# uC.net
KiCad netlist of a schematic drawn in Altium Designer
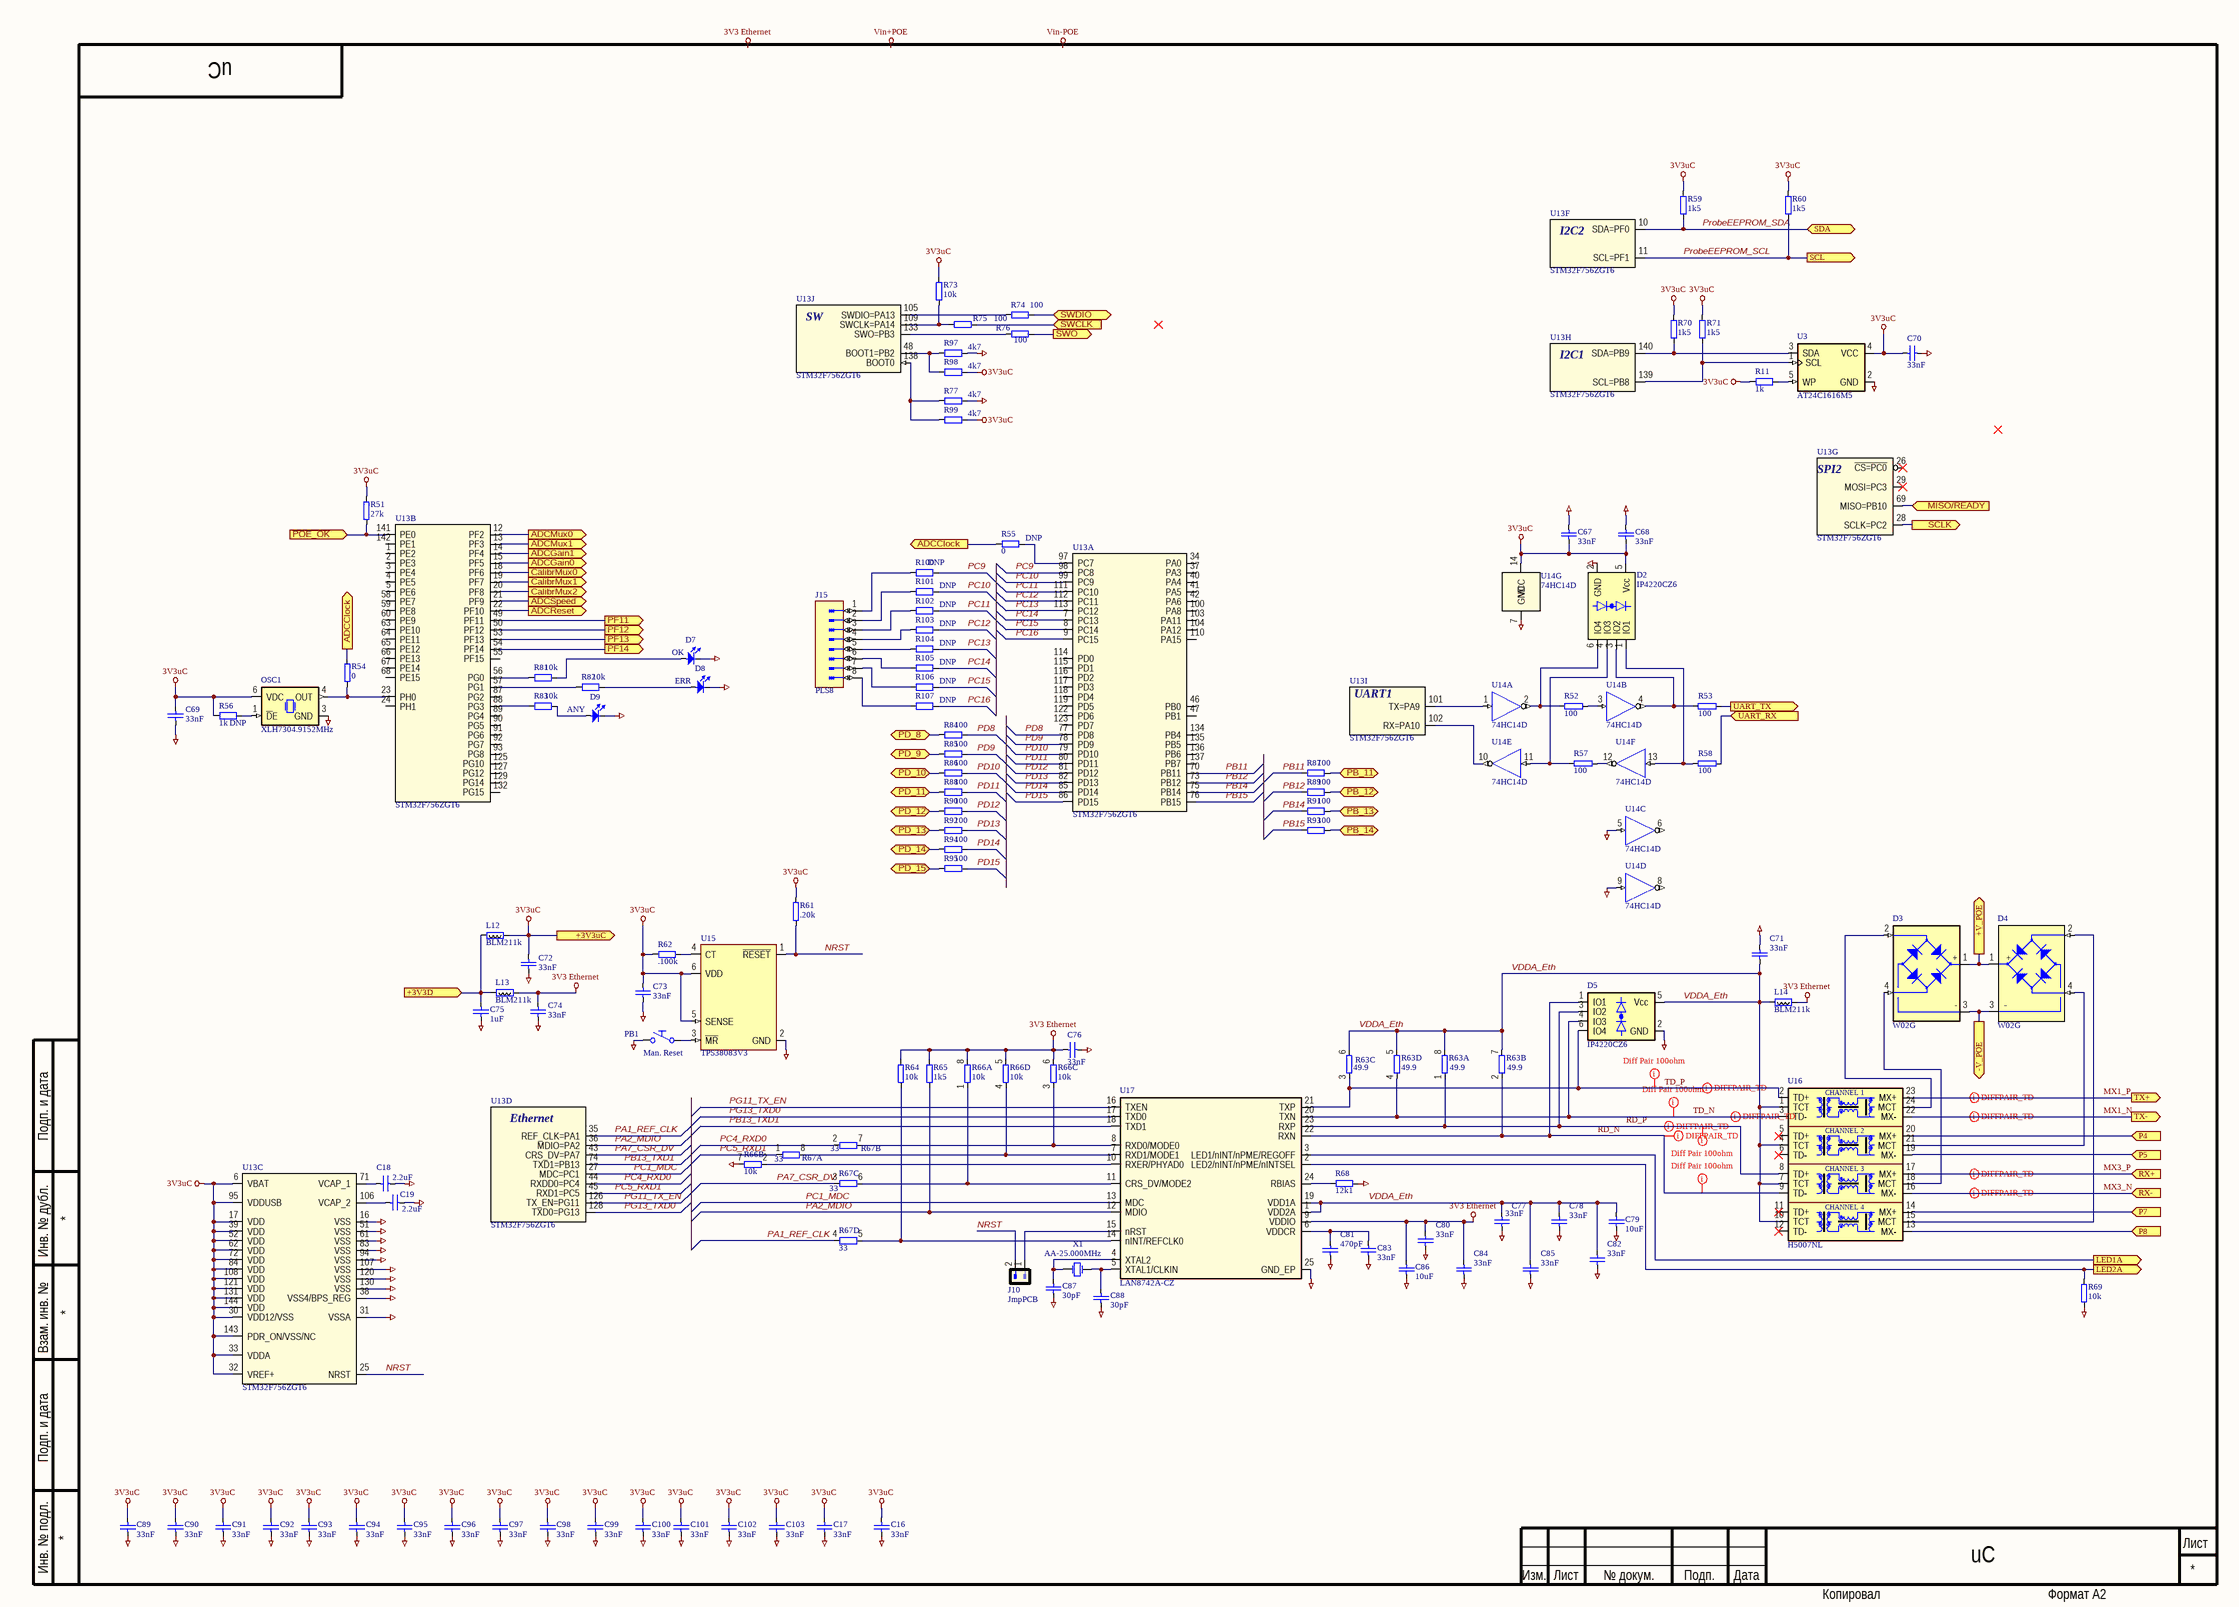
[diagram p0: uC.SchDoc]

(export (version "E")
  (design (tool "Eeschema 10.0.6"))
  (components
    (comp (ref "C16")
      (value "33nF")
      (footprint "CAPC1608X87N")
      (description "Чип конденсатор 0603")
      (fields (field (name "VOLTAGE") "50V") (field (name "TOLERANCE") "20%"))
      (libsource (lib "DDSintLib") (part "C0603"))
    )
    (comp (ref "C17")
      (value "33nF")
      (footprint "CAPC1608X87N")
      (description "Чип конденсатор 0603")
      (fields (field (name "VOLTAGE") "50V") (field (name "TOLERANCE") "20%"))
      (libsource (lib "DDSintLib") (part "C0603"))
    )
    (comp (ref "C18")
      (value "2.2uF")
      (footprint "SMD0805CAP")
      (description "Чип конденсатор 0805")
      (fields (field (name "VOLTAGE") "25V") (field (name "TOLERANCE") "20%"))
      (libsource (lib "DDSintLib") (part "C0805"))
    )
    (comp (ref "C19")
      (value "2.2uF")
      (footprint "SMD0805CAP")
      (description "Чип конденсатор 0805")
      (fields (field (name "VOLTAGE") "25V") (field (name "TOLERANCE") "20%"))
      (libsource (lib "DDSintLib") (part "C0805"))
    )
    (comp (ref "C67")
      (value "33nF")
      (footprint "CAPC1608X87N")
      (description "Чип конденсатор 0603")
      (fields (field (name "VOLTAGE") "50V") (field (name "TOLERANCE") "20%"))
      (libsource (lib "DDSintLib") (part "C0603"))
    )
    (comp (ref "C68")
      (value "33nF")
      (footprint "CAPC1608X87N")
      (description "Чип конденсатор 0603")
      (fields (field (name "VOLTAGE") "50V") (field (name "TOLERANCE") "20%"))
      (libsource (lib "DDSintLib") (part "C0603"))
    )
    (comp (ref "C69")
      (value "33nF")
      (footprint "CAPC1608X87N")
      (description "Чип конденсатор 0603")
      (fields (field (name "VOLTAGE") "50V") (field (name "TOLERANCE") "20%"))
      (libsource (lib "DDSintLib") (part "C0603"))
    )
    (comp (ref "C70")
      (value "33nF")
      (footprint "CAPC1608X87N")
      (description "Чип конденсатор 0603")
      (fields (field (name "VOLTAGE") "50V") (field (name "TOLERANCE") "20%"))
      (libsource (lib "DDSintLib") (part "C0603"))
    )
    (comp (ref "C71")
      (value "33nF")
      (footprint "CAPC1608X87N")
      (description "Чип конденсатор 0603")
      (fields (field (name "VOLTAGE") "50V") (field (name "TOLERANCE") "20%"))
      (libsource (lib "DDSintLib") (part "C0603"))
    )
    (comp (ref "C72")
      (value "33nF")
      (footprint "CAPC1608X87N")
      (description "Чип конденсатор 0603")
      (fields (field (name "VOLTAGE") "50V") (field (name "TOLERANCE") "20%"))
      (libsource (lib "DDSintLib") (part "C0603"))
    )
    (comp (ref "C73")
      (value "33nF")
      (footprint "CAPC1608X87N")
      (description "Чип конденсатор 0603")
      (fields (field (name "VOLTAGE") "50V") (field (name "TOLERANCE") "20%"))
      (libsource (lib "DDSintLib") (part "C0603"))
    )
    (comp (ref "C74")
      (value "33nF")
      (footprint "CAPC1608X87N")
      (description "Чип конденсатор 0603")
      (fields (field (name "VOLTAGE") "50V") (field (name "TOLERANCE") "20%"))
      (libsource (lib "DDSintLib") (part "C0603"))
    )
    (comp (ref "C75")
      (value "1uF")
      (footprint "CAPC1608X87N")
      (description "Чип конденсатор 0603")
      (fields (field (name "VOLTAGE") "50V") (field (name "TOLERANCE") "20%"))
      (libsource (lib "DDSintLib") (part "C0603"))
    )
    (comp (ref "C76")
      (value "33nF")
      (footprint "CAPC1608X87N")
      (description "Чип конденсатор 0603")
      (fields (field (name "VOLTAGE") "50V") (field (name "TOLERANCE") "20%"))
      (libsource (lib "DDSintLib") (part "C0603"))
    )
    (comp (ref "C77")
      (value "33nF")
      (footprint "CAPC1608X87N")
      (description "Чип конденсатор 0603")
      (fields (field (name "VOLTAGE") "50V") (field (name "TOLERANCE") "20%"))
      (libsource (lib "DDSintLib") (part "C0603"))
    )
    (comp (ref "C78")
      (value "33nF")
      (footprint "CAPC1608X87N")
      (description "Чип конденсатор 0603")
      (fields (field (name "VOLTAGE") "50V") (field (name "TOLERANCE") "20%"))
      (libsource (lib "DDSintLib") (part "C0603"))
    )
    (comp (ref "C79")
      (value "10uF")
      (footprint "SMD0805CAP")
      (description "Чип конденсатор 0805")
      (fields (field (name "VOLTAGE") "25V") (field (name "TOLERANCE") "20%"))
      (libsource (lib "DDSintLib") (part "C0805"))
    )
    (comp (ref "C80")
      (value "33nF")
      (footprint "CAPC1608X87N")
      (description "Чип конденсатор 0603")
      (fields (field (name "VOLTAGE") "50V") (field (name "TOLERANCE") "20%"))
      (libsource (lib "DDSintLib") (part "C0603"))
    )
    (comp (ref "C81")
      (value "470pF")
      (footprint "CAPC1608X87N")
      (description "Чип конденсатор 0603")
      (fields (field (name "VOLTAGE") "50V") (field (name "TOLERANCE") "20%"))
      (libsource (lib "DDSintLib") (part "C0603"))
    )
    (comp (ref "C82")
      (value "33nF")
      (footprint "CAPC1608X87N")
      (description "Чип конденсатор 0603")
      (fields (field (name "VOLTAGE") "50V") (field (name "TOLERANCE") "20%"))
      (libsource (lib "DDSintLib") (part "C0603"))
    )
    (comp (ref "C83")
      (value "33nF")
      (footprint "CAPC1608X87N")
      (description "Чип конденсатор 0603")
      (fields (field (name "VOLTAGE") "50V") (field (name "TOLERANCE") "20%"))
      (libsource (lib "DDSintLib") (part "C0603"))
    )
    (comp (ref "C84")
      (value "33nF")
      (footprint "CAPC1608X87N")
      (description "Чип конденсатор 0603")
      (fields (field (name "VOLTAGE") "50V") (field (name "TOLERANCE") "20%"))
      (libsource (lib "DDSintLib") (part "C0603"))
    )
    (comp (ref "C85")
      (value "33nF")
      (footprint "CAPC1608X87N")
      (description "Чип конденсатор 0603")
      (fields (field (name "VOLTAGE") "50V") (field (name "TOLERANCE") "20%"))
      (libsource (lib "DDSintLib") (part "C0603"))
    )
    (comp (ref "C86")
      (value "10uF")
      (footprint "SMD0805CAP")
      (description "Чип конденсатор 0805")
      (fields (field (name "VOLTAGE") "25V") (field (name "TOLERANCE") "20%"))
      (libsource (lib "DDSintLib") (part "C0805"))
    )
    (comp (ref "C87")
      (value "30pF")
      (footprint "CAPC1608X87N")
      (description "Чип конденсатор 0603")
      (fields (field (name "VOLTAGE") "50V") (field (name "TOLERANCE") "20%"))
      (libsource (lib "DDSintLib") (part "C0603"))
    )
    (comp (ref "C88")
      (value "30pF")
      (footprint "CAPC1608X87N")
      (description "Чип конденсатор 0603")
      (fields (field (name "VOLTAGE") "50V") (field (name "TOLERANCE") "20%"))
      (libsource (lib "DDSintLib") (part "C0603"))
    )
    (comp (ref "C89")
      (value "33nF")
      (footprint "CAPC1608X87N")
      (description "Чип конденсатор 0603")
      (fields (field (name "VOLTAGE") "50V") (field (name "TOLERANCE") "20%"))
      (libsource (lib "DDSintLib") (part "C0603"))
    )
    (comp (ref "C90")
      (value "33nF")
      (footprint "CAPC1608X87N")
      (description "Чип конденсатор 0603")
      (fields (field (name "VOLTAGE") "50V") (field (name "TOLERANCE") "20%"))
      (libsource (lib "DDSintLib") (part "C0603"))
    )
    (comp (ref "C91")
      (value "33nF")
      (footprint "CAPC1608X87N")
      (description "Чип конденсатор 0603")
      (fields (field (name "VOLTAGE") "50V") (field (name "TOLERANCE") "20%"))
      (libsource (lib "DDSintLib") (part "C0603"))
    )
    (comp (ref "C92")
      (value "33nF")
      (footprint "CAPC1608X87N")
      (description "Чип конденсатор 0603")
      (fields (field (name "VOLTAGE") "50V") (field (name "TOLERANCE") "20%"))
      (libsource (lib "DDSintLib") (part "C0603"))
    )
    (comp (ref "C93")
      (value "33nF")
      (footprint "CAPC1608X87N")
      (description "Чип конденсатор 0603")
      (fields (field (name "VOLTAGE") "50V") (field (name "TOLERANCE") "20%"))
      (libsource (lib "DDSintLib") (part "C0603"))
    )
    (comp (ref "C94")
      (value "33nF")
      (footprint "CAPC1608X87N")
      (description "Чип конденсатор 0603")
      (fields (field (name "VOLTAGE") "50V") (field (name "TOLERANCE") "20%"))
      (libsource (lib "DDSintLib") (part "C0603"))
    )
    (comp (ref "C95")
      (value "33nF")
      (footprint "CAPC1608X87N")
      (description "Чип конденсатор 0603")
      (fields (field (name "VOLTAGE") "50V") (field (name "TOLERANCE") "20%"))
      (libsource (lib "DDSintLib") (part "C0603"))
    )
    (comp (ref "C96")
      (value "33nF")
      (footprint "CAPC1608X87N")
      (description "Чип конденсатор 0603")
      (fields (field (name "VOLTAGE") "50V") (field (name "TOLERANCE") "20%"))
      (libsource (lib "DDSintLib") (part "C0603"))
    )
    (comp (ref "C97")
      (value "33nF")
      (footprint "CAPC1608X87N")
      (description "Чип конденсатор 0603")
      (fields (field (name "VOLTAGE") "50V") (field (name "TOLERANCE") "20%"))
      (libsource (lib "DDSintLib") (part "C0603"))
    )
    (comp (ref "C98")
      (value "33nF")
      (footprint "CAPC1608X87N")
      (description "Чип конденсатор 0603")
      (fields (field (name "VOLTAGE") "50V") (field (name "TOLERANCE") "20%"))
      (libsource (lib "DDSintLib") (part "C0603"))
    )
    (comp (ref "C99")
      (value "33nF")
      (footprint "CAPC1608X87N")
      (description "Чип конденсатор 0603")
      (fields (field (name "VOLTAGE") "50V") (field (name "TOLERANCE") "20%"))
      (libsource (lib "DDSintLib") (part "C0603"))
    )
    (comp (ref "C100")
      (value "33nF")
      (footprint "CAPC1608X87N")
      (description "Чип конденсатор 0603")
      (fields (field (name "VOLTAGE") "50V") (field (name "TOLERANCE") "20%"))
      (libsource (lib "DDSintLib") (part "C0603"))
    )
    (comp (ref "C101")
      (value "33nF")
      (footprint "CAPC1608X87N")
      (description "Чип конденсатор 0603")
      (fields (field (name "VOLTAGE") "50V") (field (name "TOLERANCE") "20%"))
      (libsource (lib "DDSintLib") (part "C0603"))
    )
    (comp (ref "C102")
      (value "33nF")
      (footprint "CAPC1608X87N")
      (description "Чип конденсатор 0603")
      (fields (field (name "VOLTAGE") "50V") (field (name "TOLERANCE") "20%"))
      (libsource (lib "DDSintLib") (part "C0603"))
    )
    (comp (ref "C103")
      (value "33nF")
      (footprint "CAPC1608X87N")
      (description "Чип конденсатор 0603")
      (fields (field (name "VOLTAGE") "50V") (field (name "TOLERANCE") "20%"))
      (libsource (lib "DDSintLib") (part "C0603"))
    )
    (comp (ref "D2")
      (value "IP4220CZ6")
      (footprint "SOT95P270X145-6N")
      (description "Optotransistor")
      (fields (field (name "VOLTAGE") "6V"))
      (libsource (lib "DDS1") (part "IP4220"))
    )
    (comp (ref "D3")
      (value "W02G")
      (footprint "RECTRON_RB15")
      (description "Diode Bridge Rectifier")
      (fields (field (name "VOLTAGE") "200V"))
      (libsource (lib "") (part "W02G_1"))
    )
    (comp (ref "D4")
      (value "W02G")
      (footprint "RECTRON_RB15")
      (description "Diode Bridge Rectifier")
      (fields (field (name "VOLTAGE") "200V"))
      (libsource (lib "DDSintLib") (part "W02G"))
    )
    (comp (ref "D5")
      (value "IP4220CZ6")
      (footprint "SOT95P270X145-6N")
      (description "Optotransistor")
      (fields (field (name "VOLTAGE") "6V"))
      (libsource (lib "DDS1") (part "IP4220"))
    )
    (comp (ref "D7")
      (value "OK")
      (footprint "LED_OSRAM_LGR971")
      (description "Чип светодиод 0805")
      (libsource (lib "DDSintLib") (part "LED0805"))
    )
    (comp (ref "D8")
      (value "ERR")
      (footprint "LED_OSRAM_LOR976")
      (description "Чип светодиод 0805")
      (libsource (lib "DDSintLib") (part "LED0805"))
    )
    (comp (ref "D9")
      (value "ANY")
      (footprint "LED_OSRAM_LYR976")
      (description "Чип светодиод 0805")
      (libsource (lib "DDSintLib") (part "LED0805"))
    )
    (comp (ref "J10")
      (value "JmpPCB")
      (footprint "PCBJumper")
      (description "PLS2")
      (libsource (lib "DDSintLib") (part "JmpPCB"))
    )
    (comp (ref "J15")
      (value "PLS8")
      (footprint "COMATEL_386.0358.1.08.440")
      (description "Вилка  PLS8/2.54")
      (libsource (lib "DDSintLib") (part "PLS8"))
    )
    (comp (ref "L12")
      (value "BLM211k")
      (footprint "RESC2012X50N")
      (description "SMD Ferrite bead 0805")
      (libsource (lib "DDSintLib") (part "BLM21"))
    )
    (comp (ref "L13")
      (value "BLM211k")
      (footprint "RESC2012X50N")
      (description "SMD Ferrite bead 0805")
      (libsource (lib "DDSintLib") (part "BLM21"))
    )
    (comp (ref "L14")
      (value "BLM211k")
      (footprint "RESC2012X50N")
      (description "SMD Ferrite bead 0805")
      (libsource (lib "DDSintLib") (part "BLM21"))
    )
    (comp (ref "OSC1")
      (value "XLH7304.9152MHz")
      (footprint "OSC_PERICOM_FRETHE025")
      (description "Генератор кварцевый")
      (libsource (lib "DDSintLib") (part "XLH730"))
    )
    (comp (ref "PB1")
      (value "Man. Reset")
      (footprint "PB_ALPS_SKHHLQA010")
      (description "Push Button Angle NO")
      (fields (field (name "Comment") "2-1825027-0"))
      (libsource (lib "DDSintLib") (part "PBAngle"))
    )
    (comp (ref "R11")
      (value "1k")
      (footprint "SMD0805RES")
      (description "Чип резистор 0805")
      (fields (field (name "TOLERANCE") "1%"))
      (libsource (lib "DDSintLib") (part "R0805"))
    )
    (comp (ref "R51")
      (value "27k")
      (footprint "SMD0805RES")
      (description "Чип резистор 0805")
      (fields (field (name "TOLERANCE") "1%"))
      (libsource (lib "DDSintLib") (part "R0805"))
    )
    (comp (ref "R52")
      (value "100")
      (footprint "SMD0805RES")
      (description "Чип резистор 0805")
      (fields (field (name "TOLERANCE") "1%"))
      (libsource (lib "DDSintLib") (part "R0805"))
    )
    (comp (ref "R53")
      (value "100")
      (footprint "SMD0805RES")
      (description "Чип резистор 0805")
      (fields (field (name "TOLERANCE") "1%"))
      (libsource (lib "DDSintLib") (part "R0805"))
    )
    (comp (ref "R54")
      (value "0")
      (footprint "SMD0805RES")
      (description "Чип резистор 0805")
      (fields (field (name "TOLERANCE") "1%"))
      (libsource (lib "DDSintLib") (part "R0805"))
    )
    (comp (ref "R55")
      (value "0")
      (footprint "SMD0805RES")
      (description "Чип резистор 0805")
      (fields (field (name "SOLDER OPTION") "DNP") (field (name "TOLERANCE") "1%"))
      (libsource (lib "DDSintLib") (part "R0805"))
    )
    (comp (ref "R56")
      (value "1k")
      (footprint "SMD0805RES")
      (description "Чип резистор 0805")
      (fields (field (name "SOLDER OPTION") "DNP") (field (name "TOLERANCE") "1%"))
      (libsource (lib "DDSintLib") (part "R0805"))
    )
    (comp (ref "R57")
      (value "100")
      (footprint "SMD0805RES")
      (description "Чип резистор 0805")
      (fields (field (name "TOLERANCE") "1%"))
      (libsource (lib "DDSintLib") (part "R0805"))
    )
    (comp (ref "R58")
      (value "100")
      (footprint "SMD0805RES")
      (description "Чип резистор 0805")
      (fields (field (name "TOLERANCE") "1%"))
      (libsource (lib "DDSintLib") (part "R0805"))
    )
    (comp (ref "R59")
      (value "1k5")
      (footprint "RESC1608X64N")
      (description "Чип резистор 0603")
      (fields (field (name "TOLERANCE") "1%"))
      (libsource (lib "DDSintLib") (part "R0603"))
    )
    (comp (ref "R60")
      (value "1k5")
      (footprint "RESC1608X64N")
      (description "Чип резистор 0603")
      (fields (field (name "TOLERANCE") "1%"))
      (libsource (lib "DDSintLib") (part "R0603"))
    )
    (comp (ref "R61")
      (value ".20k")
      (footprint "RESC1608X64N")
      (description "Чип резистор 0603")
      (fields (field (name "TOLERANCE") "1%"))
      (libsource (lib "DDSintLib") (part "R0603"))
    )
    (comp (ref "R62")
      (value ".100k")
      (footprint "RESC1608X64N")
      (description "Чип резистор 0603")
      (fields (field (name "TOLERANCE") "1%"))
      (libsource (lib "DDSintLib") (part "R0603"))
    )
    (comp (ref "R63")
      (value "49.9")
      (footprint "CAY16x4")
      (description "Сборка из 4х чип резисторов")
      (fields (field (name "TOLERANCE") "5%"))
      (libsource (lib "DDSintLib") (part "CAY16"))
    )
    (comp (ref "R64")
      (value "10k")
      (footprint "RESC1608X64N")
      (description "Чип резистор 0603")
      (fields (field (name "TOLERANCE") "1%"))
      (libsource (lib "DDSintLib") (part "R0603"))
    )
    (comp (ref "R65")
      (value "1k5")
      (footprint "RESC1608X64N")
      (description "Чип резистор 0603")
      (fields (field (name "TOLERANCE") "1%"))
      (libsource (lib "DDSintLib") (part "R0603"))
    )
    (comp (ref "R66")
      (value "10k")
      (footprint "CAY16x4")
      (description "Сборка из 4х чип резисторов")
      (fields (field (name "TOLERANCE") "5%"))
      (libsource (lib "DDSintLib") (part "CAY16"))
    )
    (comp (ref "R67")
      (value "33")
      (footprint "CAY16x4")
      (description "Сборка из 4х чип резисторов")
      (fields (field (name "TOLERANCE") "5%"))
      (libsource (lib "DDSintLib") (part "CAY16"))
    )
    (comp (ref "R68")
      (value "12k1")
      (footprint "RESC1608X64N")
      (description "Чип резистор 0603")
      (fields (field (name "TOLERANCE") "1%"))
      (libsource (lib "DDSintLib") (part "R0603"))
    )
    (comp (ref "R69")
      (value "10k")
      (footprint "RESC1608X64N")
      (description "Чип резистор 0603")
      (fields (field (name "TOLERANCE") "1%"))
      (libsource (lib "DDSintLib") (part "R0603"))
    )
    (comp (ref "R70")
      (value "1k5")
      (footprint "RESC1608X64N")
      (description "Чип резистор 0603")
      (fields (field (name "TOLERANCE") "1%"))
      (libsource (lib "DDSintLib") (part "R0603"))
    )
    (comp (ref "R71")
      (value "1k5")
      (footprint "SMD0805RES")
      (description "Чип резистор 0805")
      (fields (field (name "TOLERANCE") "1%"))
      (libsource (lib "DDSintLib") (part "R0805"))
    )
    (comp (ref "R73")
      (value "10k")
      (footprint "SMD0805RES")
      (description "Чип резистор 0805")
      (fields (field (name "TOLERANCE") "1%"))
      (libsource (lib "DDSintLib") (part "R0805"))
    )
    (comp (ref "R74")
      (value "100")
      (footprint "SMD0805RES")
      (description "Чип резистор 0805")
      (fields (field (name "TOLERANCE") "1%"))
      (libsource (lib "DDSintLib") (part "R0805"))
    )
    (comp (ref "R75")
      (value "100")
      (footprint "SMD0805RES")
      (description "Чип резистор 0805")
      (fields (field (name "TOLERANCE") "1%"))
      (libsource (lib "DDSintLib") (part "R0805"))
    )
    (comp (ref "R76")
      (value "100")
      (footprint "SMD0805RES")
      (description "Чип резистор 0805")
      (fields (field (name "TOLERANCE") "1%"))
      (libsource (lib "DDSintLib") (part "R0805"))
    )
    (comp (ref "R77")
      (value "4k7")
      (footprint "RESC1608X64N")
      (description "Чип резистор 0603")
      (fields (field (name "TOLERANCE") "1%"))
      (libsource (lib "DDSintLib") (part "R0603"))
    )
    (comp (ref "R81")
      (value "10k")
      (footprint "SMD0805RES")
      (description "Чип резистор 0805")
      (fields (field (name "TOLERANCE") "1%"))
      (libsource (lib "DDSintLib") (part "R0805"))
    )
    (comp (ref "R82")
      (value "10k")
      (footprint "SMD0805RES")
      (description "Чип резистор 0805")
      (fields (field (name "TOLERANCE") "1%"))
      (libsource (lib "DDSintLib") (part "R0805"))
    )
    (comp (ref "R83")
      (value "10k")
      (footprint "SMD0805RES")
      (description "Чип резистор 0805")
      (fields (field (name "TOLERANCE") "1%"))
      (libsource (lib "DDSintLib") (part "R0805"))
    )
    (comp (ref "R84")
      (value "100")
      (footprint "SMD0805RES")
      (description "Чип резистор 0805")
      (fields (field (name "TOLERANCE") "1%"))
      (libsource (lib "DDSintLib") (part "R0805"))
    )
    (comp (ref "R85")
      (value "100")
      (footprint "SMD0805RES")
      (description "Чип резистор 0805")
      (fields (field (name "TOLERANCE") "1%"))
      (libsource (lib "DDSintLib") (part "R0805"))
    )
    (comp (ref "R86")
      (value "100")
      (footprint "SMD0805RES")
      (description "Чип резистор 0805")
      (fields (field (name "TOLERANCE") "1%"))
      (libsource (lib "DDSintLib") (part "R0805"))
    )
    (comp (ref "R87")
      (value "100")
      (footprint "SMD0805RES")
      (description "Чип резистор 0805")
      (fields (field (name "TOLERANCE") "1%"))
      (libsource (lib "DDSintLib") (part "R0805"))
    )
    (comp (ref "R88")
      (value "100")
      (footprint "SMD0805RES")
      (description "Чип резистор 0805")
      (fields (field (name "TOLERANCE") "1%"))
      (libsource (lib "DDSintLib") (part "R0805"))
    )
    (comp (ref "R89")
      (value "100")
      (footprint "SMD0805RES")
      (description "Чип резистор 0805")
      (fields (field (name "TOLERANCE") "1%"))
      (libsource (lib "DDSintLib") (part "R0805"))
    )
    (comp (ref "R90")
      (value "100")
      (footprint "SMD0805RES")
      (description "Чип резистор 0805")
      (fields (field (name "TOLERANCE") "1%"))
      (libsource (lib "DDSintLib") (part "R0805"))
    )
    (comp (ref "R91")
      (value "100")
      (footprint "SMD0805RES")
      (description "Чип резистор 0805")
      (fields (field (name "TOLERANCE") "1%"))
      (libsource (lib "DDSintLib") (part "R0805"))
    )
    (comp (ref "R92")
      (value "100")
      (footprint "SMD0805RES")
      (description "Чип резистор 0805")
      (fields (field (name "TOLERANCE") "1%"))
      (libsource (lib "DDSintLib") (part "R0805"))
    )
    (comp (ref "R93")
      (value "100")
      (footprint "SMD0805RES")
      (description "Чип резистор 0805")
      (fields (field (name "TOLERANCE") "1%"))
      (libsource (lib "DDSintLib") (part "R0805"))
    )
    (comp (ref "R94")
      (value "100")
      (footprint "SMD0805RES")
      (description "Чип резистор 0805")
      (fields (field (name "TOLERANCE") "1%"))
      (libsource (lib "DDSintLib") (part "R0805"))
    )
    (comp (ref "R95")
      (value "100")
      (footprint "SMD0805RES")
      (description "Чип резистор 0805")
      (fields (field (name "TOLERANCE") "1%"))
      (libsource (lib "DDSintLib") (part "R0805"))
    )
    (comp (ref "R97")
      (value "4k7")
      (footprint "RESC1608X64N")
      (description "Чип резистор 0603")
      (fields (field (name "TOLERANCE") "1%"))
      (libsource (lib "DDSintLib") (part "R0603"))
    )
    (comp (ref "R98")
      (value "4k7")
      (footprint "RESC1608X64N")
      (description "Чип резистор 0603")
      (fields (field (name "TOLERANCE") "1%"))
      (libsource (lib "DDSintLib") (part "R0603"))
    )
    (comp (ref "R99")
      (value "4k7")
      (footprint "RESC1608X64N")
      (description "Чип резистор 0603")
      (fields (field (name "TOLERANCE") "1%"))
      (libsource (lib "DDSintLib") (part "R0603"))
    )
    (comp (ref "R100")
      (value "DNP")
      (footprint "RESC1608X64N")
      (description "Чип резистор 0603")
      (fields (field (name "TOLERANCE") "1%"))
      (libsource (lib "DDSintLib") (part "R0603"))
    )
    (comp (ref "R101")
      (value "DNP")
      (footprint "RESC1608X64N")
      (description "Чип резистор 0603")
      (fields (field (name "TOLERANCE") "1%"))
      (libsource (lib "DDSintLib") (part "R0603"))
    )
    (comp (ref "R102")
      (value "DNP")
      (footprint "RESC1608X64N")
      (description "Чип резистор 0603")
      (fields (field (name "TOLERANCE") "1%"))
      (libsource (lib "DDSintLib") (part "R0603"))
    )
    (comp (ref "R103")
      (value "DNP")
      (footprint "RESC1608X64N")
      (description "Чип резистор 0603")
      (fields (field (name "TOLERANCE") "1%"))
      (libsource (lib "DDSintLib") (part "R0603"))
    )
    (comp (ref "R104")
      (value "DNP")
      (footprint "RESC1608X64N")
      (description "Чип резистор 0603")
      (fields (field (name "TOLERANCE") "1%"))
      (libsource (lib "DDSintLib") (part "R0603"))
    )
    (comp (ref "R105")
      (value "DNP")
      (footprint "RESC1608X64N")
      (description "Чип резистор 0603")
      (fields (field (name "TOLERANCE") "1%"))
      (libsource (lib "DDSintLib") (part "R0603"))
    )
    (comp (ref "R106")
      (value "DNP")
      (footprint "RESC1608X64N")
      (description "Чип резистор 0603")
      (fields (field (name "TOLERANCE") "1%"))
      (libsource (lib "DDSintLib") (part "R0603"))
    )
    (comp (ref "R107")
      (value "DNP")
      (footprint "RESC1608X64N")
      (description "Чип резистор 0603")
      (fields (field (name "TOLERANCE") "1%"))
      (libsource (lib "DDSintLib") (part "R0603"))
    )
    (comp (ref "U3")
      (value "AT24C1616M5")
      (footprint "SOT23-5")
      (description "Isolateted DC DC 5V->5V or 3V3 60mA")
      (libsource (lib "DDSintLib") (part "AT24C"))
    )
    (comp (ref "U13")
      (value "STM32F756ZGT6")
      (footprint "LQFP-144_STM-M")
      (fields (field (name "COPYRIGHT") "Copyright (C) 2025 Ultra Librarian. All rights reserved."))
      (libsource (lib "") (part "STM32F756ZGT6_1"))
    )
    (comp (ref "U14")
      (value "74HC14D")
      (footprint "SOIC127P600X175-14N")
      (description "6 триггеров Шмита с инверсией.")
      (fields (field (name "VOLTAGE") "2.. 6V"))
      (libsource (lib "") (part "74HC14D_1"))
    )
    (comp (ref "U15")
      (value "TPS38083V3")
      (footprint "SOT95P270X145-6N")
      (description "Supervisory Circuit. Low-Quiescent-Current, Programmable-Delay")
      (libsource (lib "DDSintLib") (part "TPS3808"))
    )
    (comp (ref "U16")
      (value "H5007NL")
      (footprint "XFMR_PULSE_H5007NL")
      (description "Ethernet transformer IEEE 802.3")
      (libsource (lib "DDS1") (part "H5007NL"))
    )
    (comp (ref "U17")
      (value "LAN8742A-CZ")
      (footprint "QFN24_0R5_4X4")
      (description "Supervisory Circuit. Low-Quiescent-Current, Programmable-Delay")
      (libsource (lib "DDS1") (part "LAN8742"))
    )
    (comp (ref "X1")
      (value "AA-25.000MHz")
      (footprint "XTAL_AA")
      (description "Резонатор кварцевый")
      (libsource (lib "DDSintLib") (part "AA-25"))
    )
  )
  (nets
    (net (code "1") (name "/+3V3D") (class "Default")
      (node (ref "C75") (pin "2") (pinfunction "2_2") (pintype "passive"))
      (node (ref "L12") (pin "1") (pinfunction "1_1") (pintype "passive"))
      (node (ref "L13") (pin "1") (pinfunction "1_1") (pintype "passive"))
    )
    (net (code "2") (name "/+V_POE") (class "Default")
      (node (ref "D3") (pin "1") (pinfunction "+_1") (pintype "power_in"))
      (node (ref "D4") (pin "1") (pinfunction "+_1") (pintype "power_in"))
    )
    (net (code "3") (name "/-V_POE") (class "Default")
      (node (ref "D3") (pin "3") (pinfunction "-_3") (pintype "power_in"))
      (node (ref "D4") (pin "3") (pinfunction "-_3") (pintype "power_in"))
    )
    (net (code "4") (name "/ADCClock") (class "Default")
      (node (ref "R54") (pin "2") (pinfunction "2_2") (pintype "passive"))
      (node (ref "R55") (pin "2") (pinfunction "2_2") (pintype "passive"))
    )
    (net (code "5") (name "/ADCGain0") (class "Default")
      (node (ref "U13") (pin "15") (pinfunction "PF5_15") (pintype "bidirectional"))
    )
    (net (code "6") (name "/ADCGain1") (class "Default")
      (node (ref "U13") (pin "14") (pinfunction "PF4_14") (pintype "bidirectional"))
    )
    (net (code "7") (name "/ADCMux0") (class "Default")
      (node (ref "U13") (pin "12") (pinfunction "PF2_12") (pintype "bidirectional"))
    )
    (net (code "8") (name "/ADCMux1") (class "Default")
      (node (ref "U13") (pin "13") (pinfunction "PF3_13") (pintype "bidirectional"))
    )
    (net (code "9") (name "/ADCReset") (class "Default")
      (node (ref "U13") (pin "22") (pinfunction "PF10_22") (pintype "bidirectional"))
    )
    (net (code "10") (name "/ADCSpeed") (class "Default")
      (node (ref "U13") (pin "21") (pinfunction "PF9_21") (pintype "bidirectional"))
    )
    (net (code "11") (name "/CalibrMux0") (class "Default")
      (node (ref "U13") (pin "18") (pinfunction "PF6_18") (pintype "bidirectional"))
    )
    (net (code "12") (name "/CalibrMux1") (class "Default")
      (node (ref "U13") (pin "19") (pinfunction "PF7_19") (pintype "bidirectional"))
    )
    (net (code "13") (name "/CalibrMux2") (class "Default")
      (node (ref "U13") (pin "20") (pinfunction "PF8_20") (pintype "bidirectional"))
    )
    (net (code "14") (name "/LED1A") (class "Default")
      (node (ref "U17") (pin "3") (pinfunction "LED1/nINT/nPME/REGOFF_3") (pintype "passive"))
    )
    (net (code "15") (name "/LED2A") (class "Default")
      (node (ref "R69") (pin "1") (pinfunction "1_1") (pintype "passive"))
      (node (ref "U17") (pin "2") (pinfunction "LED2/nINT/nPME/nINTSEL_2") (pintype "passive"))
    )
    (net (code "16") (name "/MISO{slash}READY") (class "Default")
      (node (ref "U13") (pin "69") (pinfunction "MISO=PB10_69") (pintype "bidirectional"))
    )
    (net (code "17") (name "/MX1_N") (class "Default")
      (node (ref "U16") (pin "22") (pinfunction "MX-_22") (pintype "bidirectional"))
    )
    (net (code "18") (name "/MX1_P") (class "Default")
      (node (ref "U16") (pin "23") (pinfunction "MX+_23") (pintype "bidirectional"))
    )
    (net (code "19") (name "/MX3_N") (class "Default")
      (node (ref "U16") (pin "16") (pinfunction "MX-_16") (pintype "bidirectional"))
    )
    (net (code "20") (name "/MX3_P") (class "Default")
      (node (ref "U16") (pin "17") (pinfunction "MX+_17") (pintype "bidirectional"))
    )
    (net (code "21") (name "/NRST") (class "Default")
      (node (ref "J10") (pin "2") (pinfunction "2_2") (pintype "bidirectional"))
      (node (ref "R61") (pin "2") (pinfunction "2_2") (pintype "passive"))
      (node (ref "U13") (pin "25") (pinfunction "NRST_25") (pintype "bidirectional"))
      (node (ref "U15") (pin "1") (pinfunction "~{RESET}_1") (pintype "open_collector"))
    )
    (net (code "22") (name "/P4") (class "Default")
      (node (ref "U16") (pin "20") (pinfunction "MX+_20") (pintype "bidirectional"))
    )
    (net (code "23") (name "/P5") (class "Default")
      (node (ref "U16") (pin "19") (pinfunction "MX-_19") (pintype "bidirectional"))
    )
    (net (code "24") (name "/P7") (class "Default")
      (node (ref "U16") (pin "14") (pinfunction "MX+_14") (pintype "bidirectional"))
    )
    (net (code "25") (name "/P8") (class "Default")
      (node (ref "U16") (pin "13") (pinfunction "MX-_13") (pintype "bidirectional"))
    )
    (net (code "26") (name "/PA1_REF_CLK") (class "Default")
      (node (ref "R67") (pin "4") (pinfunction "4_4") (pintype "passive"))
      (node (ref "U13") (pin "35") (pinfunction "REF_CLK=PA1_35") (pintype "bidirectional"))
    )
    (net (code "27") (name "/PA2_MDIO") (class "Default")
      (node (ref "R65") (pin "2") (pinfunction "2_2") (pintype "passive"))
      (node (ref "U13") (pin "36") (pinfunction "MDIO=PA2_36") (pintype "bidirectional"))
      (node (ref "U17") (pin "12") (pinfunction "MDIO_12") (pintype "passive"))
    )
    (net (code "28") (name "/PA7_CSR_DV") (class "Default")
      (node (ref "R67") (pin "3") (pinfunction "3_3") (pintype "passive"))
      (node (ref "U13") (pin "43") (pinfunction "CRS_DV=PA7_43") (pintype "bidirectional"))
    )
    (net (code "29") (name "/PB11") (class "Default")
      (node (ref "R87") (pin "1") (pinfunction "1_1") (pintype "passive"))
      (node (ref "U13") (pin "70") (pinfunction "PB11_70") (pintype "bidirectional"))
    )
    (net (code "30") (name "/PB12") (class "Default")
      (node (ref "R89") (pin "1") (pinfunction "1_1") (pintype "passive"))
      (node (ref "U13") (pin "73") (pinfunction "PB12_73") (pintype "bidirectional"))
    )
    (net (code "31") (name "/PB13_TXD1") (class "Default")
      (node (ref "U13") (pin "74") (pinfunction "TXD1=PB13_74") (pintype "bidirectional"))
      (node (ref "U17") (pin "18") (pinfunction "TXD1_18") (pintype "passive"))
    )
    (net (code "32") (name "/PB14") (class "Default")
      (node (ref "R91") (pin "1") (pinfunction "1_1") (pintype "passive"))
      (node (ref "U13") (pin "75") (pinfunction "PB14_75") (pintype "bidirectional"))
    )
    (net (code "33") (name "/PB15") (class "Default")
      (node (ref "R93") (pin "1") (pinfunction "1_1") (pintype "passive"))
      (node (ref "U13") (pin "76") (pinfunction "PB15_76") (pintype "bidirectional"))
    )
    (net (code "34") (name "/PB_11") (class "Default")
      (node (ref "R87") (pin "2") (pinfunction "2_2") (pintype "passive"))
    )
    (net (code "35") (name "/PB_12") (class "Default")
      (node (ref "R89") (pin "2") (pinfunction "2_2") (pintype "passive"))
    )
    (net (code "36") (name "/PB_13") (class "Default")
      (node (ref "R91") (pin "2") (pinfunction "2_2") (pintype "passive"))
    )
    (net (code "37") (name "/PB_14") (class "Default")
      (node (ref "R93") (pin "2") (pinfunction "2_2") (pintype "passive"))
    )
    (net (code "38") (name "/PC1_MDC") (class "Default")
      (node (ref "U13") (pin "27") (pinfunction "MDC=PC1_27") (pintype "bidirectional"))
      (node (ref "U17") (pin "13") (pinfunction "MDC_13") (pintype "passive"))
    )
    (net (code "39") (name "/PC4_RXD0") (class "Default")
      (node (ref "R67") (pin "2") (pinfunction "2_2") (pintype "passive"))
      (node (ref "U13") (pin "44") (pinfunction "RXDD0=PC4_44") (pintype "bidirectional"))
    )
    (net (code "40") (name "/PC5_RXD1") (class "Default")
      (node (ref "R67") (pin "1") (pinfunction "1_1") (pintype "passive"))
      (node (ref "U13") (pin "45") (pinfunction "RXD1=PC5_45") (pintype "bidirectional"))
    )
    (net (code "41") (name "/PC9") (class "Default")
      (node (ref "R100") (pin "2") (pinfunction "2_2") (pintype "passive"))
      (node (ref "U13") (pin "98") (pinfunction "PC8_98") (pintype "bidirectional"))
    )
    (net (code "42") (name "/PC10") (class "Default")
      (node (ref "R101") (pin "2") (pinfunction "2_2") (pintype "passive"))
      (node (ref "U13") (pin "99") (pinfunction "PC9_99") (pintype "bidirectional"))
    )
    (net (code "43") (name "/PC11") (class "Default")
      (node (ref "R102") (pin "2") (pinfunction "2_2") (pintype "passive"))
      (node (ref "U13") (pin "111") (pinfunction "PC10_111") (pintype "bidirectional"))
    )
    (net (code "44") (name "/PC12") (class "Default")
      (node (ref "R103") (pin "2") (pinfunction "2_2") (pintype "passive"))
      (node (ref "U13") (pin "112") (pinfunction "PC11_112") (pintype "bidirectional"))
    )
    (net (code "45") (name "/PC13") (class "Default")
      (node (ref "R104") (pin "2") (pinfunction "2_2") (pintype "passive"))
      (node (ref "U13") (pin "113") (pinfunction "PC12_113") (pintype "bidirectional"))
    )
    (net (code "46") (name "/PC14") (class "Default")
      (node (ref "R105") (pin "2") (pinfunction "2_2") (pintype "passive"))
      (node (ref "U13") (pin "7") (pinfunction "PC13_7") (pintype "bidirectional"))
    )
    (net (code "47") (name "/PC15") (class "Default")
      (node (ref "R106") (pin "2") (pinfunction "2_2") (pintype "passive"))
      (node (ref "U13") (pin "8") (pinfunction "PC14_8") (pintype "bidirectional"))
    )
    (net (code "48") (name "/PC16") (class "Default")
      (node (ref "R107") (pin "2") (pinfunction "2_2") (pintype "passive"))
      (node (ref "U13") (pin "9") (pinfunction "PC15_9") (pintype "bidirectional"))
    )
    (net (code "49") (name "/PD8") (class "Default")
      (node (ref "R84") (pin "2") (pinfunction "2_2") (pintype "passive"))
      (node (ref "U13") (pin "77") (pinfunction "PD8_77") (pintype "bidirectional"))
    )
    (net (code "50") (name "/PD9") (class "Default")
      (node (ref "R85") (pin "2") (pinfunction "2_2") (pintype "passive"))
      (node (ref "U13") (pin "78") (pinfunction "PD9_78") (pintype "bidirectional"))
    )
    (net (code "51") (name "/PD10") (class "Default")
      (node (ref "R86") (pin "2") (pinfunction "2_2") (pintype "passive"))
      (node (ref "U13") (pin "79") (pinfunction "PD10_79") (pintype "bidirectional"))
    )
    (net (code "52") (name "/PD11") (class "Default")
      (node (ref "R88") (pin "2") (pinfunction "2_2") (pintype "passive"))
      (node (ref "U13") (pin "80") (pinfunction "PD11_80") (pintype "bidirectional"))
    )
    (net (code "53") (name "/PD12") (class "Default")
      (node (ref "R90") (pin "2") (pinfunction "2_2") (pintype "passive"))
      (node (ref "U13") (pin "81") (pinfunction "PD12_81") (pintype "bidirectional"))
    )
    (net (code "54") (name "/PD13") (class "Default")
      (node (ref "R92") (pin "2") (pinfunction "2_2") (pintype "passive"))
      (node (ref "U13") (pin "82") (pinfunction "PD13_82") (pintype "bidirectional"))
    )
    (net (code "55") (name "/PD14") (class "Default")
      (node (ref "R94") (pin "2") (pinfunction "2_2") (pintype "passive"))
      (node (ref "U13") (pin "85") (pinfunction "PD14_85") (pintype "bidirectional"))
    )
    (net (code "56") (name "/PD15") (class "Default")
      (node (ref "R95") (pin "2") (pinfunction "2_2") (pintype "passive"))
      (node (ref "U13") (pin "86") (pinfunction "PD15_86") (pintype "bidirectional"))
    )
    (net (code "57") (name "/PD_8") (class "Default")
      (node (ref "R84") (pin "1") (pinfunction "1_1") (pintype "passive"))
    )
    (net (code "58") (name "/PD_9") (class "Default")
      (node (ref "R85") (pin "1") (pinfunction "1_1") (pintype "passive"))
    )
    (net (code "59") (name "/PD_10") (class "Default")
      (node (ref "R86") (pin "1") (pinfunction "1_1") (pintype "passive"))
    )
    (net (code "60") (name "/PD_11") (class "Default")
      (node (ref "R88") (pin "1") (pinfunction "1_1") (pintype "passive"))
    )
    (net (code "61") (name "/PD_12") (class "Default")
      (node (ref "R90") (pin "1") (pinfunction "1_1") (pintype "passive"))
    )
    (net (code "62") (name "/PD_13") (class "Default")
      (node (ref "R92") (pin "1") (pinfunction "1_1") (pintype "passive"))
    )
    (net (code "63") (name "/PD_14") (class "Default")
      (node (ref "R94") (pin "1") (pinfunction "1_1") (pintype "passive"))
    )
    (net (code "64") (name "/PD_15") (class "Default")
      (node (ref "R95") (pin "1") (pinfunction "1_1") (pintype "passive"))
    )
    (net (code "65") (name "/PF11") (class "Default")
      (node (ref "U13") (pin "49") (pinfunction "PF11_49") (pintype "bidirectional"))
    )
    (net (code "66") (name "/PF12") (class "Default")
      (node (ref "U13") (pin "50") (pinfunction "PF12_50") (pintype "bidirectional"))
    )
    (net (code "67") (name "/PF13") (class "Default")
      (node (ref "U13") (pin "53") (pinfunction "PF13_53") (pintype "bidirectional"))
    )
    (net (code "68") (name "/PF14") (class "Default")
      (node (ref "U13") (pin "54") (pinfunction "PF14_54") (pintype "bidirectional"))
    )
    (net (code "69") (name "/PG11_TX_EN") (class "Default")
      (node (ref "U13") (pin "126") (pinfunction "TX_EN=PG11_126") (pintype "bidirectional"))
      (node (ref "U17") (pin "16") (pinfunction "TXEN_16") (pintype "passive"))
    )
    (net (code "70") (name "/PG13_TXD0") (class "Default")
      (node (ref "U13") (pin "128") (pinfunction "TXD0=PG13_128") (pintype "bidirectional"))
      (node (ref "U17") (pin "17") (pinfunction "TXD0_17") (pintype "passive"))
    )
    (net (code "71") (name "/POE_OK") (class "Default")
      (node (ref "R51") (pin "1") (pinfunction "1_1") (pintype "passive"))
      (node (ref "U13") (pin "141") (pinfunction "PE0_141") (pintype "bidirectional"))
    )
    (net (code "72") (name "/ProbeEEPROM_SCL") (class "Default")
      (node (ref "R60") (pin "2") (pinfunction "2_2") (pintype "passive"))
      (node (ref "U13") (pin "11") (pinfunction "SCL=PF1_11") (pintype "bidirectional"))
    )
    (net (code "73") (name "/ProbeEEPROM_SDA") (class "Default")
      (node (ref "R59") (pin "2") (pinfunction "2_2") (pintype "passive"))
      (node (ref "U13") (pin "10") (pinfunction "SDA=PF0_10") (pintype "bidirectional"))
    )
    (net (code "74") (name "/RD_N") (class "Default")
      (node (ref "D5") (pin "1") (pinfunction "IO1_1") (pintype "passive"))
      (node (ref "R63") (pin "2") (pinfunction "2_2") (pintype "passive"))
      (node (ref "U16") (pin "9") (pinfunction "TD-_9") (pintype "bidirectional"))
      (node (ref "U17") (pin "22") (pinfunction "RXN_22") (pintype "passive"))
    )
    (net (code "75") (name "/RD_P") (class "Default")
      (node (ref "D5") (pin "3") (pinfunction "IO2_3") (pintype "passive"))
      (node (ref "R63") (pin "1") (pinfunction "1_1") (pintype "passive"))
      (node (ref "U16") (pin "8") (pinfunction "TD+_8") (pintype "bidirectional"))
      (node (ref "U17") (pin "23") (pinfunction "RXP_23") (pintype "passive"))
    )
    (net (code "76") (name "/SCLK") (class "Default")
      (node (ref "U13") (pin "28") (pinfunction "SCLK=PC2_28") (pintype "bidirectional"))
    )
    (net (code "77") (name "/SWCLK") (class "Default")
      (node (ref "R75") (pin "2") (pinfunction "2_2") (pintype "passive"))
    )
    (net (code "78") (name "/SWDIO") (class "Default")
      (node (ref "R74") (pin "2") (pinfunction "2_2") (pintype "passive"))
    )
    (net (code "79") (name "/SWO") (class "Default")
      (node (ref "R76") (pin "2") (pinfunction "2_2") (pintype "passive"))
    )
    (net (code "80") (name "/TD_N") (class "Default")
      (node (ref "D5") (pin "4") (pinfunction "IO3_4") (pintype "passive"))
      (node (ref "R63") (pin "4") (pinfunction "4_4") (pintype "passive"))
      (node (ref "U16") (pin "3") (pinfunction "TD-_3") (pintype "bidirectional"))
      (node (ref "U17") (pin "20") (pinfunction "TXN_20") (pintype "passive"))
    )
    (net (code "81") (name "/TD_P") (class "Default")
      (node (ref "D5") (pin "6") (pinfunction "IO4_6") (pintype "passive"))
      (node (ref "R63") (pin "3") (pinfunction "3_3") (pintype "passive"))
      (node (ref "U16") (pin "2") (pinfunction "TD+_2") (pintype "bidirectional"))
      (node (ref "U17") (pin "21") (pinfunction "TXP_21") (pintype "passive"))
    )
    (net (code "82") (name "/UART_RX") (class "Default")
      (node (ref "R58") (pin "2") (pinfunction "2_2") (pintype "passive"))
    )
    (net (code "83") (name "/UART_TX") (class "Default")
      (node (ref "R53") (pin "2") (pinfunction "2_2") (pintype "passive"))
    )
    (net (code "84") (name "/VDDA_Eth") (class "Default")
      (node (ref "C71") (pin "1") (pinfunction "1_1") (pintype "passive"))
      (node (ref "C77") (pin "2") (pinfunction "2_2") (pintype "passive"))
      (node (ref "C78") (pin "2") (pinfunction "2_2") (pintype "passive"))
      (node (ref "C79") (pin "2") (pinfunction "2_2") (pintype "passive"))
      (node (ref "C82") (pin "2") (pinfunction "2_2") (pintype "passive"))
      (node (ref "C85") (pin "2") (pinfunction "2_2") (pintype "passive"))
      (node (ref "D5") (pin "5") (pinfunction "Vcc_5") (pintype "passive"))
      (node (ref "L14") (pin "1") (pinfunction "1_1") (pintype "passive"))
      (node (ref "R63") (pin "5") (pinfunction "5_5") (pintype "passive"))
      (node (ref "R63") (pin "6") (pinfunction "6_6") (pintype "passive"))
      (node (ref "R63") (pin "7") (pinfunction "7_7") (pintype "passive"))
      (node (ref "R63") (pin "8") (pinfunction "8_8") (pintype "passive"))
      (node (ref "U16") (pin "1") (pinfunction "TCT_1") (pintype "bidirectional"))
      (node (ref "U16") (pin "10") (pinfunction "TCT_10") (pintype "bidirectional"))
      (node (ref "U16") (pin "4") (pinfunction "TCT_4") (pintype "bidirectional"))
      (node (ref "U16") (pin "7") (pinfunction "TCT_7") (pintype "bidirectional"))
      (node (ref "U17") (pin "1") (pinfunction "VDD2A_1") (pintype "passive"))
      (node (ref "U17") (pin "19") (pinfunction "VDD1A_19") (pintype "passive"))
    )
    (net (code "85") (name "3V3 Ethernet") (class "Default")
      (node (ref "C74") (pin "2") (pinfunction "2_2") (pintype "passive"))
      (node (ref "C76") (pin "2") (pinfunction "2_2") (pintype "passive"))
      (node (ref "C80") (pin "2") (pinfunction "2_2") (pintype "passive"))
      (node (ref "C84") (pin "2") (pinfunction "2_2") (pintype "passive"))
      (node (ref "C86") (pin "2") (pinfunction "2_2") (pintype "passive"))
      (node (ref "L13") (pin "2") (pinfunction "2_2") (pintype "passive"))
      (node (ref "L14") (pin "2") (pinfunction "2_2") (pintype "passive"))
      (node (ref "R64") (pin "1") (pinfunction "1_1") (pintype "passive"))
      (node (ref "R65") (pin "1") (pinfunction "1_1") (pintype "passive"))
      (node (ref "R66") (pin "5") (pinfunction "5_5") (pintype "passive"))
      (node (ref "R66") (pin "6") (pinfunction "6_6") (pintype "passive"))
      (node (ref "R66") (pin "8") (pinfunction "8_8") (pintype "passive"))
      (node (ref "U17") (pin "9") (pinfunction "VDDIO_9") (pintype "passive"))
    )
    (net (code "86") (name "3V3uC") (class "Default")
      (node (ref "C100") (pin "2") (pinfunction "2_2") (pintype "passive"))
      (node (ref "C101") (pin "2") (pinfunction "2_2") (pintype "passive"))
      (node (ref "C102") (pin "2") (pinfunction "2_2") (pintype "passive"))
      (node (ref "C103") (pin "2") (pinfunction "2_2") (pintype "passive"))
      (node (ref "C16") (pin "2") (pinfunction "2_2") (pintype "passive"))
      (node (ref "C17") (pin "2") (pinfunction "2_2") (pintype "passive"))
      (node (ref "C67") (pin "2") (pinfunction "2_2") (pintype "passive"))
      (node (ref "C68") (pin "2") (pinfunction "2_2") (pintype "passive"))
      (node (ref "C69") (pin "2") (pinfunction "2_2") (pintype "passive"))
      (node (ref "C70") (pin "1") (pinfunction "1_1") (pintype "passive"))
      (node (ref "C72") (pin "2") (pinfunction "2_2") (pintype "passive"))
      (node (ref "C73") (pin "2") (pinfunction "2_2") (pintype "passive"))
      (node (ref "C89") (pin "2") (pinfunction "2_2") (pintype "passive"))
      (node (ref "C90") (pin "2") (pinfunction "2_2") (pintype "passive"))
      (node (ref "C91") (pin "2") (pinfunction "2_2") (pintype "passive"))
      (node (ref "C92") (pin "2") (pinfunction "2_2") (pintype "passive"))
      (node (ref "C93") (pin "2") (pinfunction "2_2") (pintype "passive"))
      (node (ref "C94") (pin "2") (pinfunction "2_2") (pintype "passive"))
      (node (ref "C95") (pin "2") (pinfunction "2_2") (pintype "passive"))
      (node (ref "C96") (pin "2") (pinfunction "2_2") (pintype "passive"))
      (node (ref "C97") (pin "2") (pinfunction "2_2") (pintype "passive"))
      (node (ref "C98") (pin "2") (pinfunction "2_2") (pintype "passive"))
      (node (ref "C99") (pin "2") (pinfunction "2_2") (pintype "passive"))
      (node (ref "D2") (pin "5") (pinfunction "Vcc_5") (pintype "passive"))
      (node (ref "L12") (pin "2") (pinfunction "2_2") (pintype "passive"))
      (node (ref "OSC1") (pin "6") (pinfunction "VDC_6") (pintype "power_in"))
      (node (ref "R11") (pin "2") (pinfunction "2_2") (pintype "passive"))
      (node (ref "R51") (pin "2") (pinfunction "2_2") (pintype "passive"))
      (node (ref "R56") (pin "1") (pinfunction "1_1") (pintype "passive"))
      (node (ref "R59") (pin "1") (pinfunction "1_1") (pintype "passive"))
      (node (ref "R60") (pin "1") (pinfunction "1_1") (pintype "passive"))
      (node (ref "R61") (pin "1") (pinfunction "1_1") (pintype "passive"))
      (node (ref "R62") (pin "1") (pinfunction "1_1") (pintype "passive"))
      (node (ref "R70") (pin "2") (pinfunction "2_2") (pintype "passive"))
      (node (ref "R71") (pin "2") (pinfunction "2_2") (pintype "passive"))
      (node (ref "R73") (pin "2") (pinfunction "2_2") (pintype "passive"))
      (node (ref "R98") (pin "2") (pinfunction "2_2") (pintype "passive"))
      (node (ref "R99") (pin "2") (pinfunction "2_2") (pintype "passive"))
      (node (ref "U13") (pin "108") (pinfunction "VDD_108") (pintype "power_in"))
      (node (ref "U13") (pin "121") (pinfunction "VDD_121") (pintype "power_in"))
      (node (ref "U13") (pin "131") (pinfunction "VDD_131") (pintype "power_in"))
      (node (ref "U13") (pin "143") (pinfunction "PDR_ON/VSS/NC_143") (pintype "bidirectional"))
      (node (ref "U13") (pin "144") (pinfunction "VDD_144") (pintype "power_in"))
      (node (ref "U13") (pin "17") (pinfunction "VDD_17") (pintype "power_in"))
      (node (ref "U13") (pin "30") (pinfunction "VDD12/VSS_30") (pintype "power_in"))
      (node (ref "U13") (pin "32") (pinfunction "VREF+_32") (pintype "power_in"))
      (node (ref "U13") (pin "33") (pinfunction "VDDA_33") (pintype "power_in"))
      (node (ref "U13") (pin "39") (pinfunction "VDD_39") (pintype "power_in"))
      (node (ref "U13") (pin "52") (pinfunction "VDD_52") (pintype "power_in"))
      (node (ref "U13") (pin "6") (pinfunction "VBAT_6") (pintype "power_in"))
      (node (ref "U13") (pin "62") (pinfunction "VDD_62") (pintype "power_in"))
      (node (ref "U13") (pin "72") (pinfunction "VDD_72") (pintype "power_in"))
      (node (ref "U13") (pin "84") (pinfunction "VDD_84") (pintype "power_in"))
      (node (ref "U13") (pin "95") (pinfunction "VDDUSB_95") (pintype "power_in"))
      (node (ref "U14") (pin "14") (pinfunction "VCC_14") (pintype "power_in"))
      (node (ref "U15") (pin "5") (pinfunction "SENSE_5") (pintype "input"))
      (node (ref "U15") (pin "6") (pinfunction "VDD_6") (pintype "power_in"))
      (node (ref "U3") (pin "4") (pinfunction "VCC_4") (pintype "power_in"))
    )
    (net (code "87") (name "GND") (class "Default")
      (node (ref "C100") (pin "1") (pinfunction "1_1") (pintype "passive"))
      (node (ref "C101") (pin "1") (pinfunction "1_1") (pintype "passive"))
      (node (ref "C102") (pin "1") (pinfunction "1_1") (pintype "passive"))
      (node (ref "C103") (pin "1") (pinfunction "1_1") (pintype "passive"))
      (node (ref "C16") (pin "1") (pinfunction "1_1") (pintype "passive"))
      (node (ref "C17") (pin "1") (pinfunction "1_1") (pintype "passive"))
      (node (ref "C18") (pin "1") (pinfunction "1_1") (pintype "passive"))
      (node (ref "C19") (pin "1") (pinfunction "1_1") (pintype "passive"))
      (node (ref "C67") (pin "1") (pinfunction "1_1") (pintype "passive"))
      (node (ref "C68") (pin "1") (pinfunction "1_1") (pintype "passive"))
      (node (ref "C69") (pin "1") (pinfunction "1_1") (pintype "passive"))
      (node (ref "C70") (pin "2") (pinfunction "2_2") (pintype "passive"))
      (node (ref "C71") (pin "2") (pinfunction "2_2") (pintype "passive"))
      (node (ref "C72") (pin "1") (pinfunction "1_1") (pintype "passive"))
      (node (ref "C73") (pin "1") (pinfunction "1_1") (pintype "passive"))
      (node (ref "C74") (pin "1") (pinfunction "1_1") (pintype "passive"))
      (node (ref "C75") (pin "1") (pinfunction "1_1") (pintype "passive"))
      (node (ref "C76") (pin "1") (pinfunction "1_1") (pintype "passive"))
      (node (ref "C77") (pin "1") (pinfunction "1_1") (pintype "passive"))
      (node (ref "C78") (pin "1") (pinfunction "1_1") (pintype "passive"))
      (node (ref "C79") (pin "1") (pinfunction "1_1") (pintype "passive"))
      (node (ref "C80") (pin "1") (pinfunction "1_1") (pintype "passive"))
      (node (ref "C81") (pin "1") (pinfunction "1_1") (pintype "passive"))
      (node (ref "C82") (pin "1") (pinfunction "1_1") (pintype "passive"))
      (node (ref "C83") (pin "1") (pinfunction "1_1") (pintype "passive"))
      (node (ref "C84") (pin "1") (pinfunction "1_1") (pintype "passive"))
      (node (ref "C85") (pin "1") (pinfunction "1_1") (pintype "passive"))
      (node (ref "C86") (pin "1") (pinfunction "1_1") (pintype "passive"))
      (node (ref "C87") (pin "2") (pinfunction "2_2") (pintype "passive"))
      (node (ref "C88") (pin "2") (pinfunction "2_2") (pintype "passive"))
      (node (ref "C89") (pin "1") (pinfunction "1_1") (pintype "passive"))
      (node (ref "C90") (pin "1") (pinfunction "1_1") (pintype "passive"))
      (node (ref "C91") (pin "1") (pinfunction "1_1") (pintype "passive"))
      (node (ref "C92") (pin "1") (pinfunction "1_1") (pintype "passive"))
      (node (ref "C93") (pin "1") (pinfunction "1_1") (pintype "passive"))
      (node (ref "C94") (pin "1") (pinfunction "1_1") (pintype "passive"))
      (node (ref "C95") (pin "1") (pinfunction "1_1") (pintype "passive"))
      (node (ref "C96") (pin "1") (pinfunction "1_1") (pintype "passive"))
      (node (ref "C97") (pin "1") (pinfunction "1_1") (pintype "passive"))
      (node (ref "C98") (pin "1") (pinfunction "1_1") (pintype "passive"))
      (node (ref "C99") (pin "1") (pinfunction "1_1") (pintype "passive"))
      (node (ref "D2") (pin "2") (pinfunction "GND_2") (pintype "passive"))
      (node (ref "D5") (pin "2") (pinfunction "GND_2") (pintype "passive"))
      (node (ref "D7") (pin "1") (pinfunction "C_1") (pintype "passive"))
      (node (ref "D8") (pin "1") (pinfunction "C_1") (pintype "passive"))
      (node (ref "D9") (pin "1") (pinfunction "C_1") (pintype "passive"))
      (node (ref "OSC1") (pin "3") (pinfunction "GND_3") (pintype "power_in"))
      (node (ref "PB1") (pin "2") (pinfunction "NO_2") (pintype "bidirectional"))
      (node (ref "R66") (pin "7") (pinfunction "7_7") (pintype "passive"))
      (node (ref "R68") (pin "1") (pinfunction "1_1") (pintype "passive"))
      (node (ref "R69") (pin "2") (pinfunction "2_2") (pintype "passive"))
      (node (ref "R77") (pin "2") (pinfunction "2_2") (pintype "passive"))
      (node (ref "R97") (pin "2") (pinfunction "2_2") (pintype "passive"))
      (node (ref "U13") (pin "107") (pinfunction "VSS_107") (pintype "power_in"))
      (node (ref "U13") (pin "120") (pinfunction "VSS_120") (pintype "power_in"))
      (node (ref "U13") (pin "130") (pinfunction "VSS_130") (pintype "power_in"))
      (node (ref "U13") (pin "16") (pinfunction "VSS_16") (pintype "power_in"))
      (node (ref "U13") (pin "31") (pinfunction "VSSA_31") (pintype "power_in"))
      (node (ref "U13") (pin "38") (pinfunction "VSS4/BPS_REG_38") (pintype "power_in"))
      (node (ref "U13") (pin "51") (pinfunction "VSS_51") (pintype "power_in"))
      (node (ref "U13") (pin "61") (pinfunction "VSS_61") (pintype "power_in"))
      (node (ref "U13") (pin "83") (pinfunction "VSS_83") (pintype "power_in"))
      (node (ref "U13") (pin "94") (pinfunction "VSS_94") (pintype "power_in"))
      (node (ref "U14") (pin "5") (pinfunction "IN_5") (pintype "input"))
      (node (ref "U14") (pin "7") (pinfunction "GND_7") (pintype "power_in"))
      (node (ref "U14") (pin "9") (pinfunction "IN_9") (pintype "input"))
      (node (ref "U15") (pin "2") (pinfunction "GND_2") (pintype "power_in"))
      (node (ref "U17") (pin "25") (pinfunction "GND_EP_25") (pintype "passive"))
      (node (ref "U3") (pin "2") (pinfunction "GND_2") (pintype "power_in"))
    )
    (net (code "88") (name "Net-(D2-IO1)") (class "Default")
      (node (ref "D2") (pin "1") (pinfunction "IO1_1") (pintype "passive"))
      (node (ref "R58") (pin "1") (pinfunction "1_1") (pintype "passive"))
      (node (ref "U14") (pin "13") (pinfunction "IN_13") (pintype "input"))
    )
    (net (code "89") (name "Net-(D2-IO2)") (class "Default")
      (node (ref "D2") (pin "3") (pinfunction "IO2_3") (pintype "passive"))
      (node (ref "R53") (pin "1") (pinfunction "1_1") (pintype "passive"))
      (node (ref "U14") (pin "4") (pinfunction "OUT_4") (pintype "output"))
    )
    (net (code "90") (name "Net-(D2-IO3)") (class "Default")
      (node (ref "D2") (pin "4") (pinfunction "IO3_4") (pintype "passive"))
      (node (ref "R57") (pin "1") (pinfunction "1_1") (pintype "passive"))
      (node (ref "U14") (pin "11") (pinfunction "IN_11") (pintype "input"))
    )
    (net (code "91") (name "Net-(D2-IO4)") (class "Default")
      (node (ref "D2") (pin "6") (pinfunction "IO4_6") (pintype "passive"))
      (node (ref "R52") (pin "1") (pinfunction "1_1") (pintype "passive"))
      (node (ref "U14") (pin "2") (pinfunction "OUT_2") (pintype "output"))
    )
    (net (code "92") (name "Net-(D3-AC-Pad2)") (class "Default")
      (node (ref "D3") (pin "2") (pinfunction "AC_2") (pintype "input"))
      (node (ref "U16") (pin "24") (pinfunction "MCT_24") (pintype "bidirectional"))
    )
    (net (code "93") (name "Net-(D3-AC-Pad4)") (class "Default")
      (node (ref "D3") (pin "4") (pinfunction "AC_4") (pintype "input"))
      (node (ref "U16") (pin "18") (pinfunction "MCT_18") (pintype "bidirectional"))
    )
    (net (code "94") (name "Net-(D4-AC-Pad2)") (class "Default")
      (node (ref "D4") (pin "2") (pinfunction "AC_2") (pintype "input"))
      (node (ref "U16") (pin "15") (pinfunction "MCT_15") (pintype "bidirectional"))
    )
    (net (code "95") (name "Net-(D4-AC-Pad4)") (class "Default")
      (node (ref "D4") (pin "4") (pinfunction "AC_4") (pintype "input"))
      (node (ref "U16") (pin "21") (pinfunction "MCT_21") (pintype "bidirectional"))
    )
    (net (code "96") (name "Net-(D7-A)") (class "Default")
      (node (ref "D7") (pin "2") (pinfunction "A_2") (pintype "passive"))
      (node (ref "R81") (pin "2") (pinfunction "2_2") (pintype "passive"))
    )
    (net (code "97") (name "Net-(D8-A)") (class "Default")
      (node (ref "D8") (pin "2") (pinfunction "A_2") (pintype "passive"))
      (node (ref "R82") (pin "2") (pinfunction "2_2") (pintype "passive"))
    )
    (net (code "98") (name "Net-(D9-A)") (class "Default")
      (node (ref "D9") (pin "2") (pinfunction "A_2") (pintype "passive"))
      (node (ref "R83") (pin "2") (pinfunction "2_2") (pintype "passive"))
    )
    (net (code "99") (name "Net-(J15-Pad1)") (class "Default")
      (node (ref "J15") (pin "1") (pinfunction "1_1") (pintype "bidirectional"))
      (node (ref "R100") (pin "1") (pinfunction "1_1") (pintype "passive"))
    )
    (net (code "100") (name "Net-(J15-Pad2)") (class "Default")
      (node (ref "J15") (pin "2") (pinfunction "2_2") (pintype "bidirectional"))
      (node (ref "R101") (pin "1") (pinfunction "1_1") (pintype "passive"))
    )
    (net (code "101") (name "Net-(J15-Pad3)") (class "Default")
      (node (ref "J15") (pin "3") (pinfunction "3_3") (pintype "bidirectional"))
      (node (ref "R102") (pin "1") (pinfunction "1_1") (pintype "passive"))
    )
    (net (code "102") (name "Net-(J15-Pad4)") (class "Default")
      (node (ref "J15") (pin "4") (pinfunction "4_4") (pintype "bidirectional"))
      (node (ref "R103") (pin "1") (pinfunction "1_1") (pintype "passive"))
    )
    (net (code "103") (name "Net-(J15-Pad5)") (class "Default")
      (node (ref "J15") (pin "5") (pinfunction "5_5") (pintype "bidirectional"))
      (node (ref "R104") (pin "1") (pinfunction "1_1") (pintype "passive"))
    )
    (net (code "104") (name "Net-(J15-Pad6)") (class "Default")
      (node (ref "J15") (pin "6") (pinfunction "6_6") (pintype "bidirectional"))
      (node (ref "R105") (pin "1") (pinfunction "1_1") (pintype "passive"))
    )
    (net (code "105") (name "Net-(J15-Pad7)") (class "Default")
      (node (ref "J15") (pin "7") (pinfunction "7_7") (pintype "bidirectional"))
      (node (ref "R106") (pin "1") (pinfunction "1_1") (pintype "passive"))
    )
    (net (code "106") (name "Net-(J15-Pad8)") (class "Default")
      (node (ref "J15") (pin "8") (pinfunction "8_8") (pintype "bidirectional"))
      (node (ref "R107") (pin "1") (pinfunction "1_1") (pintype "passive"))
    )
    (net (code "107") (name "Net-(OSC1-OUT)") (class "Default")
      (node (ref "OSC1") (pin "4") (pinfunction "OUT_4") (pintype "output"))
      (node (ref "R54") (pin "1") (pinfunction "1_1") (pintype "passive"))
      (node (ref "U13") (pin "23") (pinfunction "PH0_23") (pintype "bidirectional"))
    )
    (net (code "108") (name "Net-(OSC1-~{D}E)") (class "Default")
      (node (ref "OSC1") (pin "1") (pinfunction "~{D}E_1") (pintype "input"))
      (node (ref "R56") (pin "2") (pinfunction "2_2") (pintype "passive"))
    )
    (net (code "109") (name "Net-(PB1-C)") (class "Default")
      (node (ref "PB1") (pin "1") (pinfunction "C_1") (pintype "bidirectional"))
      (node (ref "U15") (pin "3") (pinfunction "~{MR}_3") (pintype "input"))
    )
    (net (code "110") (name "Net-(U3-WP)") (class "Default")
      (node (ref "R11") (pin "1") (pinfunction "1_1") (pintype "passive"))
      (node (ref "U3") (pin "5") (pinfunction "WP_5") (pintype "input"))
    )
    (net (code "111") (name "Net-(U13A-PC7)") (class "Default")
      (node (ref "R55") (pin "1") (pinfunction "1_1") (pintype "passive"))
      (node (ref "U13") (pin "97") (pinfunction "PC7_97") (pintype "bidirectional"))
    )
    (net (code "112") (name "Net-(U13B-PG0)") (class "Default")
      (node (ref "R81") (pin "1") (pinfunction "1_1") (pintype "passive"))
      (node (ref "U13") (pin "56") (pinfunction "PG0_56") (pintype "bidirectional"))
    )
    (net (code "113") (name "Net-(U13B-PG1)") (class "Default")
      (node (ref "R82") (pin "1") (pinfunction "1_1") (pintype "passive"))
      (node (ref "U13") (pin "57") (pinfunction "PG1_57") (pintype "bidirectional"))
    )
    (net (code "114") (name "Net-(U13B-PG3)") (class "Default")
      (node (ref "R83") (pin "1") (pinfunction "1_1") (pintype "passive"))
      (node (ref "U13") (pin "88") (pinfunction "PG3_88") (pintype "bidirectional"))
    )
    (net (code "115") (name "Net-(U13C-VCAP_1)") (class "Default")
      (node (ref "C18") (pin "2") (pinfunction "2_2") (pintype "passive"))
      (node (ref "U13") (pin "71") (pinfunction "VCAP_1_71") (pintype "power_in"))
    )
    (net (code "116") (name "Net-(U13C-VCAP_2)") (class "Default")
      (node (ref "C19") (pin "2") (pinfunction "2_2") (pintype "passive"))
      (node (ref "U13") (pin "106") (pinfunction "VCAP_2_106") (pintype "power_in"))
    )
    (net (code "117") (name "Net-(U13H-SCL=PB8)") (class "Default")
      (node (ref "R71") (pin "1") (pinfunction "1_1") (pintype "passive"))
      (node (ref "U13") (pin "139") (pinfunction "SCL=PB8_139") (pintype "bidirectional"))
      (node (ref "U3") (pin "1") (pinfunction "SCL_1") (pintype "input"))
    )
    (net (code "118") (name "Net-(U13H-SDA=PB9)") (class "Default")
      (node (ref "R70") (pin "1") (pinfunction "1_1") (pintype "passive"))
      (node (ref "U13") (pin "140") (pinfunction "SDA=PB9_140") (pintype "bidirectional"))
      (node (ref "U3") (pin "3") (pinfunction "SDA_3") (pintype "bidirectional"))
    )
    (net (code "119") (name "Net-(U13I-RX=PA10)") (class "Default")
      (node (ref "U13") (pin "102") (pinfunction "RX=PA10_102") (pintype "bidirectional"))
      (node (ref "U14") (pin "10") (pinfunction "OUT_10") (pintype "output"))
    )
    (net (code "120") (name "Net-(U13I-TX=PA9)") (class "Default")
      (node (ref "U13") (pin "101") (pinfunction "TX=PA9_101") (pintype "bidirectional"))
      (node (ref "U14") (pin "1") (pinfunction "IN_1") (pintype "input"))
    )
    (net (code "121") (name "Net-(U13J-BOOT0)") (class "Default")
      (node (ref "R77") (pin "1") (pinfunction "1_1") (pintype "passive"))
      (node (ref "R99") (pin "1") (pinfunction "1_1") (pintype "passive"))
      (node (ref "U13") (pin "138") (pinfunction "BOOT0_138") (pintype "input"))
    )
    (net (code "122") (name "Net-(U13J-BOOT1=PB2)") (class "Default")
      (node (ref "R97") (pin "1") (pinfunction "1_1") (pintype "passive"))
      (node (ref "R98") (pin "1") (pinfunction "1_1") (pintype "passive"))
      (node (ref "U13") (pin "48") (pinfunction "BOOT1=PB2_48") (pintype "bidirectional"))
    )
    (net (code "123") (name "Net-(U13J-SWCLK=PA14)") (class "Default")
      (node (ref "R73") (pin "1") (pinfunction "1_1") (pintype "passive"))
      (node (ref "R75") (pin "1") (pinfunction "1_1") (pintype "passive"))
      (node (ref "U13") (pin "109") (pinfunction "SWCLK=PA14_109") (pintype "bidirectional"))
    )
    (net (code "124") (name "Net-(U13J-SWDIO=PA13)") (class "Default")
      (node (ref "R74") (pin "1") (pinfunction "1_1") (pintype "passive"))
      (node (ref "U13") (pin "105") (pinfunction "SWDIO=PA13_105") (pintype "bidirectional"))
    )
    (net (code "125") (name "Net-(U13J-SWO=PB3)") (class "Default")
      (node (ref "R76") (pin "1") (pinfunction "1_1") (pintype "passive"))
      (node (ref "U13") (pin "133") (pinfunction "SWO=PB3_133") (pintype "bidirectional"))
    )
    (net (code "126") (name "Net-(U14B-IN)") (class "Default")
      (node (ref "R52") (pin "2") (pinfunction "2_2") (pintype "passive"))
      (node (ref "U14") (pin "3") (pinfunction "IN_3") (pintype "input"))
    )
    (net (code "127") (name "Net-(U14F-OUT)") (class "Default")
      (node (ref "R57") (pin "2") (pinfunction "2_2") (pintype "passive"))
      (node (ref "U14") (pin "12") (pinfunction "OUT_12") (pintype "output"))
    )
    (net (code "128") (name "Net-(U15-CT)") (class "Default")
      (node (ref "R62") (pin "2") (pinfunction "2_2") (pintype "passive"))
      (node (ref "U15") (pin "4") (pinfunction "CT_4") (pintype "passive"))
    )
    (net (code "129") (name "Net-(U17-CRS_DV{slash}MODE2)") (class "Default")
      (node (ref "R66") (pin "1") (pinfunction "1_1") (pintype "passive"))
      (node (ref "R67") (pin "6") (pinfunction "6_6") (pintype "passive"))
      (node (ref "U17") (pin "11") (pinfunction "CRS_DV/MODE2_11") (pintype "passive"))
    )
    (net (code "130") (name "Net-(U17-RBIAS)") (class "Default")
      (node (ref "R68") (pin "2") (pinfunction "2_2") (pintype "passive"))
      (node (ref "U17") (pin "24") (pinfunction "RBIAS_24") (pintype "passive"))
    )
    (net (code "131") (name "Net-(U17-RXD0{slash}MODE0)") (class "Default")
      (node (ref "R66") (pin "3") (pinfunction "3_3") (pintype "passive"))
      (node (ref "R67") (pin "7") (pinfunction "7_7") (pintype "passive"))
      (node (ref "U17") (pin "8") (pinfunction "RXD0/MODE0_8") (pintype "passive"))
    )
    (net (code "132") (name "Net-(U17-RXD1{slash}MODE1)") (class "Default")
      (node (ref "R66") (pin "4") (pinfunction "4_4") (pintype "passive"))
      (node (ref "R67") (pin "8") (pinfunction "8_8") (pintype "passive"))
      (node (ref "U17") (pin "7") (pinfunction "RXD1/MODE1_7") (pintype "passive"))
    )
    (net (code "133") (name "Net-(U17-RXER{slash}PHYAD0)") (class "Default")
      (node (ref "R66") (pin "2") (pinfunction "2_2") (pintype "passive"))
      (node (ref "U17") (pin "10") (pinfunction "RXER/PHYAD0_10") (pintype "passive"))
    )
    (net (code "134") (name "Net-(U17-VDDCR)") (class "Default")
      (node (ref "C81") (pin "2") (pinfunction "2_2") (pintype "passive"))
      (node (ref "C83") (pin "2") (pinfunction "2_2") (pintype "passive"))
      (node (ref "U17") (pin "6") (pinfunction "VDDCR_6") (pintype "passive"))
    )
    (net (code "135") (name "Net-(U17-XTAL1{slash}CLKIN)") (class "Default")
      (node (ref "C88") (pin "1") (pinfunction "1_1") (pintype "passive"))
      (node (ref "U17") (pin "5") (pinfunction "XTAL1/CLKIN_5") (pintype "passive"))
      (node (ref "X1") (pin "2") (pinfunction "OSC2_2") (pintype "passive"))
    )
    (net (code "136") (name "Net-(U17-XTAL2)") (class "Default")
      (node (ref "C87") (pin "1") (pinfunction "1_1") (pintype "passive"))
      (node (ref "U17") (pin "4") (pinfunction "XTAL2_4") (pintype "passive"))
      (node (ref "X1") (pin "1") (pinfunction "OSC1_1") (pintype "passive"))
    )
    (net (code "137") (name "Net-(U17-nINT{slash}REFCLK0)") (class "Default")
      (node (ref "R64") (pin "2") (pinfunction "2_2") (pintype "passive"))
      (node (ref "R67") (pin "5") (pinfunction "5_5") (pintype "passive"))
      (node (ref "U17") (pin "14") (pinfunction "nINT/REFCLK0_14") (pintype "passive"))
    )
    (net (code "138") (name "Net-(U17-nRST)") (class "Default")
      (node (ref "J10") (pin "1") (pinfunction "1_1") (pintype "bidirectional"))
      (node (ref "U17") (pin "15") (pinfunction "nRST_15") (pintype "passive"))
    )
    (net (code "141") (name "unconnected-(U13A-PA0-Pad34)") (class "Default")
      (node (ref "U13") (pin "34") (pinfunction "PA0_34") (pintype "bidirectional"))
    )
    (net (code "142") (name "unconnected-(U13A-PA3-Pad37)") (class "Default")
      (node (ref "U13") (pin "37") (pinfunction "PA3_37") (pintype "bidirectional"))
    )
    (net (code "143") (name "unconnected-(U13A-PA4-Pad40)") (class "Default")
      (node (ref "U13") (pin "40") (pinfunction "PA4_40") (pintype "bidirectional"))
    )
    (net (code "144") (name "unconnected-(U13A-PA5-Pad41)") (class "Default")
      (node (ref "U13") (pin "41") (pinfunction "PA5_41") (pintype "bidirectional"))
    )
    (net (code "145") (name "unconnected-(U13A-PA6-Pad42)") (class "Default")
      (node (ref "U13") (pin "42") (pinfunction "PA6_42") (pintype "bidirectional"))
    )
    (net (code "146") (name "unconnected-(U13A-PA8-Pad100)") (class "Default")
      (node (ref "U13") (pin "100") (pinfunction "PA8_100") (pintype "bidirectional"))
    )
    (net (code "147") (name "unconnected-(U13A-PA11-Pad103)") (class "Default")
      (node (ref "U13") (pin "103") (pinfunction "PA11_103") (pintype "bidirectional"))
    )
    (net (code "148") (name "unconnected-(U13A-PA12-Pad104)") (class "Default")
      (node (ref "U13") (pin "104") (pinfunction "PA12_104") (pintype "bidirectional"))
    )
    (net (code "149") (name "unconnected-(U13A-PA15-Pad110)") (class "Default")
      (node (ref "U13") (pin "110") (pinfunction "PA15_110") (pintype "bidirectional"))
    )
    (net (code "150") (name "unconnected-(U13A-PB0-Pad46)") (class "Default")
      (node (ref "U13") (pin "46") (pinfunction "PB0_46") (pintype "bidirectional"))
    )
    (net (code "151") (name "unconnected-(U13A-PB1-Pad47)") (class "Default")
      (node (ref "U13") (pin "47") (pinfunction "PB1_47") (pintype "bidirectional"))
    )
    (net (code "152") (name "unconnected-(U13A-PB4-Pad134)") (class "Default")
      (node (ref "U13") (pin "134") (pinfunction "PB4_134") (pintype "bidirectional"))
    )
    (net (code "153") (name "unconnected-(U13A-PB5-Pad135)") (class "Default")
      (node (ref "U13") (pin "135") (pinfunction "PB5_135") (pintype "bidirectional"))
    )
    (net (code "154") (name "unconnected-(U13A-PB6-Pad136)") (class "Default")
      (node (ref "U13") (pin "136") (pinfunction "PB6_136") (pintype "bidirectional"))
    )
    (net (code "155") (name "unconnected-(U13A-PB7-Pad137)") (class "Default")
      (node (ref "U13") (pin "137") (pinfunction "PB7_137") (pintype "bidirectional"))
    )
    (net (code "156") (name "unconnected-(U13A-PD0-Pad114)") (class "Default")
      (node (ref "U13") (pin "114") (pinfunction "PD0_114") (pintype "bidirectional"))
    )
    (net (code "157") (name "unconnected-(U13A-PD1-Pad115)") (class "Default")
      (node (ref "U13") (pin "115") (pinfunction "PD1_115") (pintype "bidirectional"))
    )
    (net (code "158") (name "unconnected-(U13A-PD2-Pad116)") (class "Default")
      (node (ref "U13") (pin "116") (pinfunction "PD2_116") (pintype "bidirectional"))
    )
    (net (code "159") (name "unconnected-(U13A-PD3-Pad117)") (class "Default")
      (node (ref "U13") (pin "117") (pinfunction "PD3_117") (pintype "bidirectional"))
    )
    (net (code "160") (name "unconnected-(U13A-PD4-Pad118)") (class "Default")
      (node (ref "U13") (pin "118") (pinfunction "PD4_118") (pintype "bidirectional"))
    )
    (net (code "161") (name "unconnected-(U13A-PD5-Pad119)") (class "Default")
      (node (ref "U13") (pin "119") (pinfunction "PD5_119") (pintype "bidirectional"))
    )
    (net (code "162") (name "unconnected-(U13A-PD6-Pad122)") (class "Default")
      (node (ref "U13") (pin "122") (pinfunction "PD6_122") (pintype "bidirectional"))
    )
    (net (code "163") (name "unconnected-(U13A-PD7-Pad123)") (class "Default")
      (node (ref "U13") (pin "123") (pinfunction "PD7_123") (pintype "bidirectional"))
    )
    (net (code "164") (name "unconnected-(U13B-PE1-Pad142)") (class "Default")
      (node (ref "U13") (pin "142") (pinfunction "PE1_142") (pintype "bidirectional"))
    )
    (net (code "165") (name "unconnected-(U13B-PE2-Pad1)") (class "Default")
      (node (ref "U13") (pin "1") (pinfunction "PE2_1") (pintype "bidirectional"))
    )
    (net (code "166") (name "unconnected-(U13B-PE3-Pad2)") (class "Default")
      (node (ref "U13") (pin "2") (pinfunction "PE3_2") (pintype "bidirectional"))
    )
    (net (code "167") (name "unconnected-(U13B-PE4-Pad3)") (class "Default")
      (node (ref "U13") (pin "3") (pinfunction "PE4_3") (pintype "bidirectional"))
    )
    (net (code "168") (name "unconnected-(U13B-PE5-Pad4)") (class "Default")
      (node (ref "U13") (pin "4") (pinfunction "PE5_4") (pintype "bidirectional"))
    )
    (net (code "169") (name "unconnected-(U13B-PE6-Pad5)") (class "Default")
      (node (ref "U13") (pin "5") (pinfunction "PE6_5") (pintype "bidirectional"))
    )
    (net (code "170") (name "unconnected-(U13B-PE7-Pad58)") (class "Default")
      (node (ref "U13") (pin "58") (pinfunction "PE7_58") (pintype "bidirectional"))
    )
    (net (code "171") (name "unconnected-(U13B-PE8-Pad59)") (class "Default")
      (node (ref "U13") (pin "59") (pinfunction "PE8_59") (pintype "bidirectional"))
    )
    (net (code "172") (name "unconnected-(U13B-PE9-Pad60)") (class "Default")
      (node (ref "U13") (pin "60") (pinfunction "PE9_60") (pintype "bidirectional"))
    )
    (net (code "173") (name "unconnected-(U13B-PE10-Pad63)") (class "Default")
      (node (ref "U13") (pin "63") (pinfunction "PE10_63") (pintype "bidirectional"))
    )
    (net (code "174") (name "unconnected-(U13B-PE11-Pad64)") (class "Default")
      (node (ref "U13") (pin "64") (pinfunction "PE11_64") (pintype "bidirectional"))
    )
    (net (code "175") (name "unconnected-(U13B-PE12-Pad65)") (class "Default")
      (node (ref "U13") (pin "65") (pinfunction "PE12_65") (pintype "bidirectional"))
    )
    (net (code "176") (name "unconnected-(U13B-PE13-Pad66)") (class "Default")
      (node (ref "U13") (pin "66") (pinfunction "PE13_66") (pintype "bidirectional"))
    )
    (net (code "177") (name "unconnected-(U13B-PE14-Pad67)") (class "Default")
      (node (ref "U13") (pin "67") (pinfunction "PE14_67") (pintype "bidirectional"))
    )
    (net (code "178") (name "unconnected-(U13B-PE15-Pad68)") (class "Default")
      (node (ref "U13") (pin "68") (pinfunction "PE15_68") (pintype "bidirectional"))
    )
    (net (code "179") (name "unconnected-(U13B-PF15-Pad55)") (class "Default")
      (node (ref "U13") (pin "55") (pinfunction "PF15_55") (pintype "bidirectional"))
    )
    (net (code "180") (name "unconnected-(U13B-PG2-Pad87)") (class "Default")
      (node (ref "U13") (pin "87") (pinfunction "PG2_87") (pintype "bidirectional"))
    )
    (net (code "181") (name "unconnected-(U13B-PG4-Pad89)") (class "Default")
      (node (ref "U13") (pin "89") (pinfunction "PG4_89") (pintype "bidirectional"))
    )
    (net (code "182") (name "unconnected-(U13B-PG5-Pad90)") (class "Default")
      (node (ref "U13") (pin "90") (pinfunction "PG5_90") (pintype "bidirectional"))
    )
    (net (code "183") (name "unconnected-(U13B-PG6-Pad91)") (class "Default")
      (node (ref "U13") (pin "91") (pinfunction "PG6_91") (pintype "bidirectional"))
    )
    (net (code "184") (name "unconnected-(U13B-PG7-Pad92)") (class "Default")
      (node (ref "U13") (pin "92") (pinfunction "PG7_92") (pintype "bidirectional"))
    )
    (net (code "185") (name "unconnected-(U13B-PG8-Pad93)") (class "Default")
      (node (ref "U13") (pin "93") (pinfunction "PG8_93") (pintype "bidirectional"))
    )
    (net (code "186") (name "unconnected-(U13B-PG10-Pad125)") (class "Default")
      (node (ref "U13") (pin "125") (pinfunction "PG10_125") (pintype "bidirectional"))
    )
    (net (code "187") (name "unconnected-(U13B-PG12-Pad127)") (class "Default")
      (node (ref "U13") (pin "127") (pinfunction "PG12_127") (pintype "bidirectional"))
    )
    (net (code "188") (name "unconnected-(U13B-PG14-Pad129)") (class "Default")
      (node (ref "U13") (pin "129") (pinfunction "PG14_129") (pintype "bidirectional"))
    )
    (net (code "189") (name "unconnected-(U13B-PG15-Pad132)") (class "Default")
      (node (ref "U13") (pin "132") (pinfunction "PG15_132") (pintype "bidirectional"))
    )
    (net (code "190") (name "unconnected-(U13B-PH1-Pad24)") (class "Default")
      (node (ref "U13") (pin "24") (pinfunction "PH1_24") (pintype "bidirectional"))
    )
    (net (code "191") (name "unconnected-(U13G-CS=PC0-Pad26)") (class "Default")
      (node (ref "U13") (pin "26") (pinfunction "CS=PC0_26") (pintype "bidirectional+no_connect"))
    )
    (net (code "192") (name "unconnected-(U13G-MOSI=PC3-Pad29)") (class "Default")
      (node (ref "U13") (pin "29") (pinfunction "MOSI=PC3_29") (pintype "bidirectional+no_connect"))
    )
    (net (code "193") (name "unconnected-(U14C-OUT-Pad6)") (class "Default")
      (node (ref "U14") (pin "6") (pinfunction "OUT_6") (pintype "output"))
    )
    (net (code "194") (name "unconnected-(U14D-OUT-Pad8)") (class "Default")
      (node (ref "U14") (pin "8") (pinfunction "OUT_8") (pintype "output"))
    )
    (net (code "195") (name "unconnected-(U16-TD+-Pad5)") (class "Default")
      (node (ref "U16") (pin "5") (pinfunction "TD+_5") (pintype "bidirectional+no_connect"))
    )
    (net (code "196") (name "unconnected-(U16-TD+-Pad11)") (class "Default")
      (node (ref "U16") (pin "11") (pinfunction "TD+_11") (pintype "bidirectional+no_connect"))
    )
    (net (code "197") (name "unconnected-(U16-TD--Pad6)") (class "Default")
      (node (ref "U16") (pin "6") (pinfunction "TD-_6") (pintype "bidirectional+no_connect"))
    )
    (net (code "198") (name "unconnected-(U16-TD--Pad12)") (class "Default")
      (node (ref "U16") (pin "12") (pinfunction "TD-_12") (pintype "bidirectional+no_connect"))
    )
  )
)
